# Sheet1.net
KiCad netlist of a schematic drawn in Altium Designer
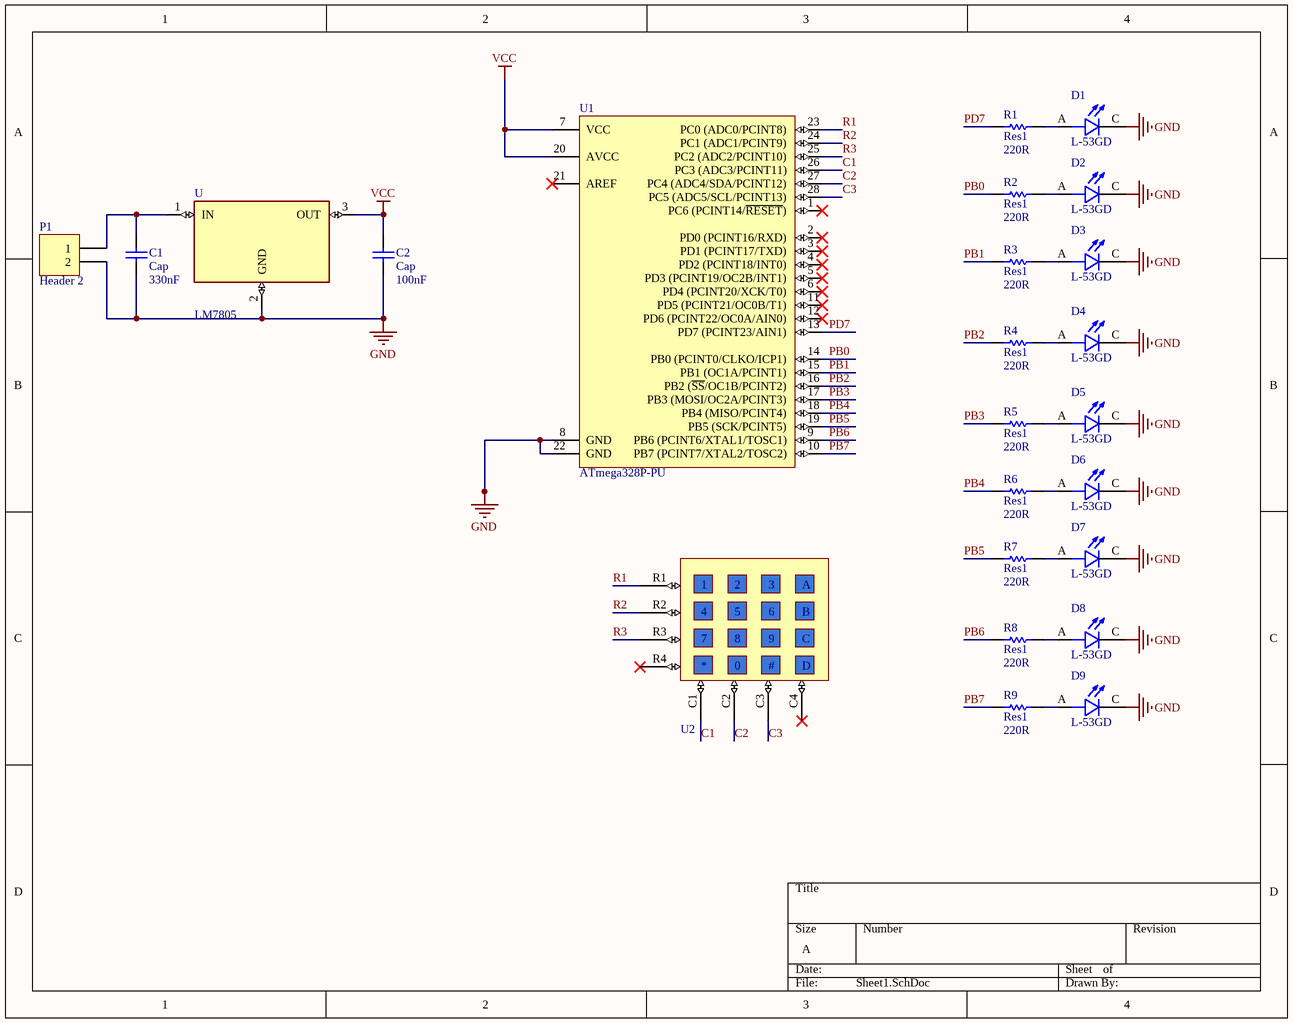
[diagram p0: Sheet1.SchDoc]

(export (version "E")
  (design (tool "Eeschema 10.0.6"))
  (components
    (comp (ref "C1")
      (value "Cap")
      (footprint "RAD-0.3")
      (description "Capacitor")
      (fields (field (name "ALTIUM_VALUE") "330nF") (field (name "PUBLISHER") "Altium Limited"))
      (libsource (lib "Miscellaneous Devices") (part "Cap"))
    )
    (comp (ref "C2")
      (value "Cap")
      (footprint "RAD-0.3")
      (description "Capacitor")
      (fields (field (name "ALTIUM_VALUE") "100nF") (field (name "PUBLISHER") "Altium Limited"))
      (libsource (lib "Miscellaneous Devices") (part "Cap"))
    )
    (comp (ref "D1")
      (value "L-53GD")
      (footprint "LEDRD254W50D500H1060")
      (description "LED; 5mm; green; 5-32mcd; 60Â°; Front: convex")
      (fields (field (name "MF") "Kingbright"))
      (libsource (lib "L-53GD") (part "L-53GD"))
    )
    (comp (ref "D2")
      (value "L-53GD")
      (footprint "LEDRD254W50D500H1060")
      (description "LED; 5mm; green; 5-32mcd; 60Â°; Front: convex")
      (fields (field (name "MF") "Kingbright"))
      (libsource (lib "L-53GD") (part "L-53GD"))
    )
    (comp (ref "D3")
      (value "L-53GD")
      (footprint "LEDRD254W50D500H1060")
      (description "LED; 5mm; green; 5-32mcd; 60Â°; Front: convex")
      (fields (field (name "MF") "Kingbright"))
      (libsource (lib "L-53GD") (part "L-53GD"))
    )
    (comp (ref "D4")
      (value "L-53GD")
      (footprint "LEDRD254W50D500H1060")
      (description "LED; 5mm; green; 5-32mcd; 60Â°; Front: convex")
      (fields (field (name "MF") "Kingbright"))
      (libsource (lib "L-53GD") (part "L-53GD"))
    )
    (comp (ref "D5")
      (value "L-53GD")
      (footprint "LEDRD254W50D500H1060")
      (description "LED; 5mm; green; 5-32mcd; 60Â°; Front: convex")
      (fields (field (name "MF") "Kingbright"))
      (libsource (lib "L-53GD") (part "L-53GD"))
    )
    (comp (ref "D6")
      (value "L-53GD")
      (footprint "LEDRD254W50D500H1060")
      (description "LED; 5mm; green; 5-32mcd; 60Â°; Front: convex")
      (fields (field (name "MF") "Kingbright"))
      (libsource (lib "L-53GD") (part "L-53GD"))
    )
    (comp (ref "D7")
      (value "L-53GD")
      (footprint "LEDRD254W50D500H1060")
      (description "LED; 5mm; green; 5-32mcd; 60Â°; Front: convex")
      (fields (field (name "MF") "Kingbright"))
      (libsource (lib "L-53GD") (part "L-53GD"))
    )
    (comp (ref "D8")
      (value "L-53GD")
      (footprint "LEDRD254W50D500H1060")
      (description "LED; 5mm; green; 5-32mcd; 60Â°; Front: convex")
      (fields (field (name "MF") "Kingbright"))
      (libsource (lib "L-53GD") (part "L-53GD"))
    )
    (comp (ref "D9")
      (value "L-53GD")
      (footprint "LEDRD254W50D500H1060")
      (description "LED; 5mm; green; 5-32mcd; 60Â°; Front: convex")
      (fields (field (name "MF") "Kingbright"))
      (libsource (lib "L-53GD") (part "L-53GD"))
    )
    (comp (ref "P1")
      (value "Header 2")
      (footprint "HDR1X2")
      (description "Header, 2-Pin")
      (fields (field (name "PUBLISHER") "Altium Limited"))
      (libsource (lib "Miscellaneous Connectors") (part "Header 2"))
    )
    (comp (ref "R1")
      (value "Res1")
      (footprint "AXIAL-0.3")
      (description "Resistor")
      (fields (field (name "ALTIUM_VALUE") "220R") (field (name "PUBLISHER") "Altium Limited"))
      (libsource (lib "Miscellaneous Devices") (part "Res1"))
    )
    (comp (ref "R2")
      (value "Res1")
      (footprint "AXIAL-0.3")
      (description "Resistor")
      (fields (field (name "ALTIUM_VALUE") "220R") (field (name "PUBLISHER") "Altium Limited"))
      (libsource (lib "Miscellaneous Devices") (part "Res1"))
    )
    (comp (ref "R3")
      (value "Res1")
      (footprint "AXIAL-0.3")
      (description "Resistor")
      (fields (field (name "ALTIUM_VALUE") "220R") (field (name "PUBLISHER") "Altium Limited"))
      (libsource (lib "Miscellaneous Devices") (part "Res1"))
    )
    (comp (ref "R4")
      (value "Res1")
      (footprint "AXIAL-0.3")
      (description "Resistor")
      (fields (field (name "ALTIUM_VALUE") "220R") (field (name "PUBLISHER") "Altium Limited"))
      (libsource (lib "Miscellaneous Devices") (part "Res1"))
    )
    (comp (ref "R5")
      (value "Res1")
      (footprint "AXIAL-0.3")
      (description "Resistor")
      (fields (field (name "ALTIUM_VALUE") "220R") (field (name "PUBLISHER") "Altium Limited"))
      (libsource (lib "Miscellaneous Devices") (part "Res1"))
    )
    (comp (ref "R6")
      (value "Res1")
      (footprint "AXIAL-0.3")
      (description "Resistor")
      (fields (field (name "ALTIUM_VALUE") "220R") (field (name "PUBLISHER") "Altium Limited"))
      (libsource (lib "Miscellaneous Devices") (part "Res1"))
    )
    (comp (ref "R7")
      (value "Res1")
      (footprint "AXIAL-0.3")
      (description "Resistor")
      (fields (field (name "ALTIUM_VALUE") "220R") (field (name "PUBLISHER") "Altium Limited"))
      (libsource (lib "Miscellaneous Devices") (part "Res1"))
    )
    (comp (ref "R8")
      (value "Res1")
      (footprint "AXIAL-0.3")
      (description "Resistor")
      (fields (field (name "ALTIUM_VALUE") "220R") (field (name "PUBLISHER") "Altium Limited"))
      (libsource (lib "Miscellaneous Devices") (part "Res1"))
    )
    (comp (ref "R9")
      (value "Res1")
      (footprint "AXIAL-0.3")
      (description "Resistor")
      (fields (field (name "ALTIUM_VALUE") "220R") (field (name "PUBLISHER") "Altium Limited"))
      (libsource (lib "Miscellaneous Devices") (part "Res1"))
    )
    (comp (ref "U")
      (value "LM7805")
      (footprint "TO220")
      (description "Linear Voltage Regulator IC 1 Output 1.5A SOT-223-4")
      (fields (field (name "MF") "Texas Instruments"))
      (libsource (lib "LM7805") (part "LM7805"))
    )
    (comp (ref "U1")
      (value "ATmega328P-PU")
      (footprint "28P3")
      (libsource (lib "Altium Content Vault") (part "MC-8B-ATM48-IL28"))
    )
    (comp (ref "U2")
      (value "keypad 4*3")
      (footprint "keypad 4*4")
      (libsource (lib "Integrated_Library1") (part "keypad 4*3"))
    )
  )
  (nets
    (net (code "1") (name "/C1") (class "Default")
      (node (ref "U1") (pin "26") (pinfunction "PC3_(ADC3/PCINT11)_26") (pintype "bidirectional"))
      (node (ref "U2") (pin "C1") (pinfunction "37_C1") (pintype "bidirectional"))
    )
    (net (code "2") (name "/C2") (class "Default")
      (node (ref "U1") (pin "27") (pinfunction "PC4_(ADC4/SDA/PCINT12)_27") (pintype "bidirectional"))
      (node (ref "U2") (pin "C2") (pinfunction "C2_C2") (pintype "bidirectional"))
    )
    (net (code "3") (name "/C3") (class "Default")
      (node (ref "U1") (pin "28") (pinfunction "PC5_(ADC5/SCL/PCINT13)_28") (pintype "bidirectional"))
      (node (ref "U2") (pin "C3") (pinfunction "39_C3") (pintype "bidirectional"))
    )
    (net (code "4") (name "/PB0") (class "Default")
      (node (ref "R2") (pin "1") (pinfunction "1_1") (pintype "passive"))
      (node (ref "U1") (pin "14") (pinfunction "PB0_(PCINT0/CLKO/ICP1)_14") (pintype "bidirectional"))
    )
    (net (code "5") (name "/PB1") (class "Default")
      (node (ref "R3") (pin "1") (pinfunction "1_1") (pintype "passive"))
      (node (ref "U1") (pin "15") (pinfunction "PB1_(OC1A/PCINT1)_15") (pintype "bidirectional"))
    )
    (net (code "6") (name "/PB2") (class "Default")
      (node (ref "R4") (pin "1") (pinfunction "1_1") (pintype "passive"))
      (node (ref "U1") (pin "16") (pinfunction "PB2_(~{SS}/OC1B/PCINT2)_16") (pintype "bidirectional"))
    )
    (net (code "7") (name "/PB3") (class "Default")
      (node (ref "R5") (pin "1") (pinfunction "1_1") (pintype "passive"))
      (node (ref "U1") (pin "17") (pinfunction "PB3_(MOSI/OC2A/PCINT3)_17") (pintype "bidirectional"))
    )
    (net (code "8") (name "/PB4") (class "Default")
      (node (ref "R6") (pin "1") (pinfunction "1_1") (pintype "passive"))
      (node (ref "U1") (pin "18") (pinfunction "PB4_(MISO/PCINT4)_18") (pintype "bidirectional"))
    )
    (net (code "9") (name "/PB5") (class "Default")
      (node (ref "R7") (pin "1") (pinfunction "1_1") (pintype "passive"))
      (node (ref "U1") (pin "19") (pinfunction "PB5_(SCK/PCINT5)_19") (pintype "bidirectional"))
    )
    (net (code "10") (name "/PB6") (class "Default")
      (node (ref "R8") (pin "1") (pinfunction "1_1") (pintype "passive"))
      (node (ref "U1") (pin "9") (pinfunction "PB6_(PCINT6/XTAL1/TOSC1)_9") (pintype "bidirectional"))
    )
    (net (code "11") (name "/PB7") (class "Default")
      (node (ref "R9") (pin "1") (pinfunction "1_1") (pintype "passive"))
      (node (ref "U1") (pin "10") (pinfunction "PB7_(PCINT7/XTAL2/TOSC2)_10") (pintype "bidirectional"))
    )
    (net (code "12") (name "/PD7") (class "Default")
      (node (ref "R1") (pin "1") (pinfunction "1_1") (pintype "passive"))
      (node (ref "U1") (pin "13") (pinfunction "PD7_(PCINT23/AIN1)_13") (pintype "bidirectional"))
    )
    (net (code "13") (name "/R1") (class "Default")
      (node (ref "U1") (pin "23") (pinfunction "PC0_(ADC0/PCINT8)_23") (pintype "bidirectional"))
      (node (ref "U2") (pin "R1") (pinfunction "1_R1") (pintype "bidirectional"))
    )
    (net (code "14") (name "/R2") (class "Default")
      (node (ref "U1") (pin "24") (pinfunction "PC1_(ADC1/PCINT9)_24") (pintype "bidirectional"))
      (node (ref "U2") (pin "R2") (pinfunction "R2_R2") (pintype "bidirectional"))
    )
    (net (code "15") (name "/R3") (class "Default")
      (node (ref "U1") (pin "25") (pinfunction "PC2_(ADC2/PCINT10)_25") (pintype "bidirectional"))
      (node (ref "U2") (pin "R3") (pinfunction "35_R3") (pintype "bidirectional"))
    )
    (net (code "16") (name "GND") (class "Default")
      (node (ref "C1") (pin "1") (pinfunction "1_1") (pintype "passive"))
      (node (ref "C2") (pin "1") (pinfunction "1_1") (pintype "passive"))
      (node (ref "D1") (pin "C") (pinfunction "C_C") (pintype "passive"))
      (node (ref "D2") (pin "C") (pinfunction "C_C") (pintype "passive"))
      (node (ref "D3") (pin "C") (pinfunction "C_C") (pintype "passive"))
      (node (ref "D4") (pin "C") (pinfunction "C_C") (pintype "passive"))
      (node (ref "D5") (pin "C") (pinfunction "C_C") (pintype "passive"))
      (node (ref "D6") (pin "C") (pinfunction "C_C") (pintype "passive"))
      (node (ref "D7") (pin "C") (pinfunction "C_C") (pintype "passive"))
      (node (ref "D8") (pin "C") (pinfunction "C_C") (pintype "passive"))
      (node (ref "D9") (pin "C") (pinfunction "C_C") (pintype "passive"))
      (node (ref "P1") (pin "2") (pinfunction "2_2") (pintype "passive"))
      (node (ref "U") (pin "2") (pinfunction "GND_2") (pintype "bidirectional"))
      (node (ref "U1") (pin "22") (pinfunction "GND_22") (pintype "power_in"))
      (node (ref "U1") (pin "8") (pinfunction "GND_8") (pintype "power_in"))
    )
    (net (code "17") (name "Net-(D1-PadA)") (class "Default")
      (node (ref "D1") (pin "A") (pinfunction "A_A") (pintype "passive"))
      (node (ref "R1") (pin "2") (pinfunction "2_2") (pintype "passive"))
    )
    (net (code "18") (name "Net-(D2-PadA)") (class "Default")
      (node (ref "D2") (pin "A") (pinfunction "A_A") (pintype "passive"))
      (node (ref "R2") (pin "2") (pinfunction "2_2") (pintype "passive"))
    )
    (net (code "19") (name "Net-(D3-PadA)") (class "Default")
      (node (ref "D3") (pin "A") (pinfunction "A_A") (pintype "passive"))
      (node (ref "R3") (pin "2") (pinfunction "2_2") (pintype "passive"))
    )
    (net (code "20") (name "Net-(D4-PadA)") (class "Default")
      (node (ref "D4") (pin "A") (pinfunction "A_A") (pintype "passive"))
      (node (ref "R4") (pin "2") (pinfunction "2_2") (pintype "passive"))
    )
    (net (code "21") (name "Net-(D5-PadA)") (class "Default")
      (node (ref "D5") (pin "A") (pinfunction "A_A") (pintype "passive"))
      (node (ref "R5") (pin "2") (pinfunction "2_2") (pintype "passive"))
    )
    (net (code "22") (name "Net-(D6-PadA)") (class "Default")
      (node (ref "D6") (pin "A") (pinfunction "A_A") (pintype "passive"))
      (node (ref "R6") (pin "2") (pinfunction "2_2") (pintype "passive"))
    )
    (net (code "23") (name "Net-(D7-PadA)") (class "Default")
      (node (ref "D7") (pin "A") (pinfunction "A_A") (pintype "passive"))
      (node (ref "R7") (pin "2") (pinfunction "2_2") (pintype "passive"))
    )
    (net (code "24") (name "Net-(D8-PadA)") (class "Default")
      (node (ref "D8") (pin "A") (pinfunction "A_A") (pintype "passive"))
      (node (ref "R8") (pin "2") (pinfunction "2_2") (pintype "passive"))
    )
    (net (code "25") (name "Net-(D9-PadA)") (class "Default")
      (node (ref "D9") (pin "A") (pinfunction "A_A") (pintype "passive"))
      (node (ref "R9") (pin "2") (pinfunction "2_2") (pintype "passive"))
    )
    (net (code "26") (name "Net-(U-IN)") (class "Default")
      (node (ref "C1") (pin "2") (pinfunction "2_2") (pintype "passive"))
      (node (ref "P1") (pin "1") (pinfunction "1_1") (pintype "passive"))
      (node (ref "U") (pin "1") (pinfunction "IN_1") (pintype "bidirectional"))
    )
    (net (code "27") (name "VCC") (class "Default")
      (node (ref "C2") (pin "2") (pinfunction "2_2") (pintype "passive"))
      (node (ref "U") (pin "3") (pinfunction "OUT_3") (pintype "bidirectional"))
      (node (ref "U1") (pin "20") (pinfunction "AVCC_20") (pintype "power_in"))
      (node (ref "U1") (pin "7") (pinfunction "VCC_7") (pintype "power_in"))
    )
    (net (code "28") (name "unconnected-(U1-AREF-Pad21)") (class "Default")
      (node (ref "U1") (pin "21") (pinfunction "AREF_21") (pintype "power_in+no_connect"))
    )
    (net (code "29") (name "unconnected-(U1-PC6_(PCINT14{slash}~{RESET})-Pad1)") (class "Default")
      (node (ref "U1") (pin "1") (pinfunction "PC6_(PCINT14/~{RESET})_1") (pintype "bidirectional+no_connect"))
    )
    (net (code "30") (name "unconnected-(U1-PD0_(PCINT16{slash}RXD)-Pad2)") (class "Default")
      (node (ref "U1") (pin "2") (pinfunction "PD0_(PCINT16/RXD)_2") (pintype "bidirectional+no_connect"))
    )
    (net (code "31") (name "unconnected-(U1-PD1_(PCINT17{slash}TXD)-Pad3)") (class "Default")
      (node (ref "U1") (pin "3") (pinfunction "PD1_(PCINT17/TXD)_3") (pintype "bidirectional+no_connect"))
    )
    (net (code "32") (name "unconnected-(U1-PD2_(PCINT18{slash}INT0)-Pad4)") (class "Default")
      (node (ref "U1") (pin "4") (pinfunction "PD2_(PCINT18/INT0)_4") (pintype "bidirectional+no_connect"))
    )
    (net (code "33") (name "unconnected-(U1-PD3_(PCINT19{slash}OC2B{slash}INT1)-Pad5)") (class "Default")
      (node (ref "U1") (pin "5") (pinfunction "PD3_(PCINT19/OC2B/INT1)_5") (pintype "bidirectional+no_connect"))
    )
    (net (code "34") (name "unconnected-(U1-PD4_(PCINT20{slash}XCK{slash}T0)-Pad6)") (class "Default")
      (node (ref "U1") (pin "6") (pinfunction "PD4_(PCINT20/XCK/T0)_6") (pintype "bidirectional+no_connect"))
    )
    (net (code "35") (name "unconnected-(U1-PD5_(PCINT21{slash}OC0B{slash}T1)-Pad11)") (class "Default")
      (node (ref "U1") (pin "11") (pinfunction "PD5_(PCINT21/OC0B/T1)_11") (pintype "bidirectional+no_connect"))
    )
    (net (code "36") (name "unconnected-(U1-PD6_(PCINT22{slash}OC0A{slash}AIN0)-Pad12)") (class "Default")
      (node (ref "U1") (pin "12") (pinfunction "PD6_(PCINT22/OC0A/AIN0)_12") (pintype "bidirectional+no_connect"))
    )
    (net (code "37") (name "unconnected-(U2-36-PadR4)") (class "Default")
      (node (ref "U2") (pin "R4") (pinfunction "36_R4") (pintype "bidirectional+no_connect"))
    )
    (net (code "38") (name "unconnected-(U2-R5-PadC4)") (class "Default")
      (node (ref "U2") (pin "C4") (pinfunction "R5_C4") (pintype "bidirectional+no_connect"))
    )
  )
)
